# 7_dout.net
KiCad netlist of a schematic drawn in Altium Designer
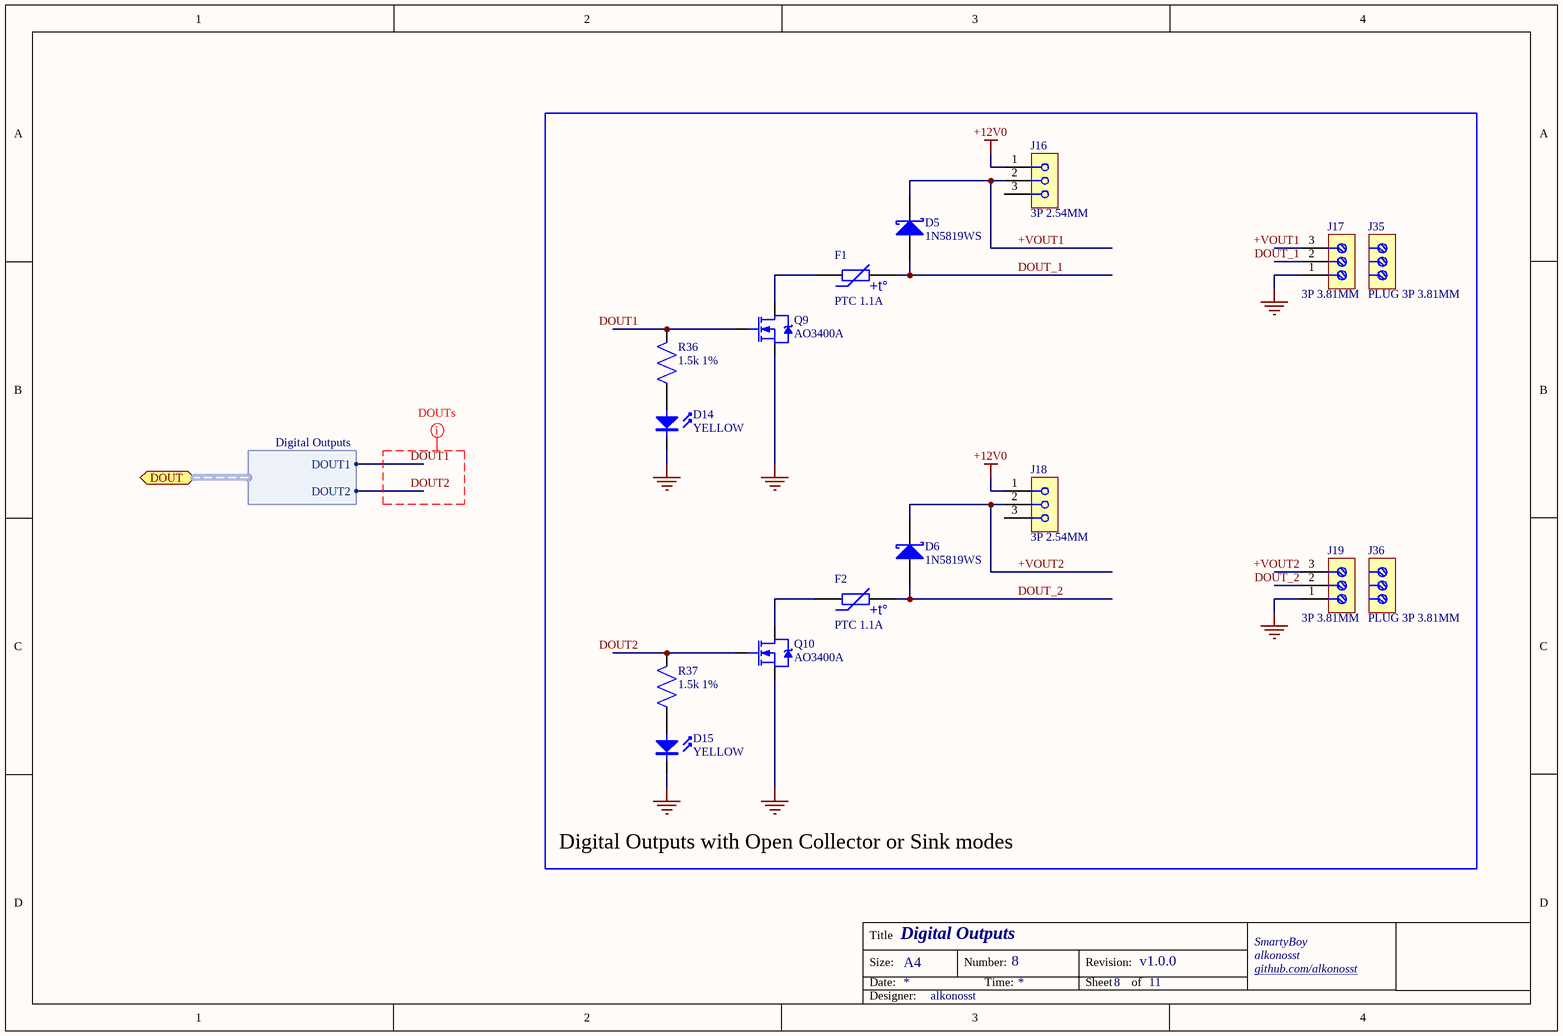
[diagram p0: 7_dout.SchDoc]

(export (version "E")
  (design (tool "Eeschema 10.0.6"))
  (components
    (comp (ref "D5")
      (value "1N5819WS")
      (footprint "SOD-323")
      (description "40V 1A 600mV @ 1A SOD-323 Schottky Barrier Diodes (SBD)")
      (fields (field (name "LCSC PART") "C191023"))
      (libsource (lib "nombre_por_definir") (part "1N5819WS"))
    )
    (comp (ref "D6")
      (value "1N5819WS")
      (footprint "SOD-323")
      (description "40V 1A 600mV @ 1A SOD-323 Schottky Barrier Diodes (SBD)")
      (fields (field (name "LCSC PART") "C191023"))
      (libsource (lib "nombre_por_definir") (part "1N5819WS"))
    )
    (comp (ref "D14")
      (value "YELLOW")
      (footprint "LED0603-YELLOW")
      (description "Yellow 585.5~591.5nm 0603 Light Emitting Diodes (LED)")
      (fields (field (name "LCSC PART") "C72038"))
      (libsource (lib "nombre_por_definir") (part "19-213/Y2C-CQ2R2L/3T(CY)"))
    )
    (comp (ref "D15")
      (value "YELLOW")
      (footprint "LED0603-YELLOW")
      (description "Yellow 585.5~591.5nm 0603 Light Emitting Diodes (LED)")
      (fields (field (name "LCSC PART") "C72038"))
      (libsource (lib "nombre_por_definir") (part "19-213/Y2C-CQ2R2L/3T(CY)"))
    )
    (comp (ref "F1")
      (value "PTC 1.1A")
      (footprint "1812L")
      (description "Polymeric 33V 200mΩ 1.95A 500ms 1812 PTC Resettable Fuses")
      (fields (field (name "LCSC PART") "C142747"))
      (libsource (lib "nombre_por_definir") (part "1812L110/33MR"))
    )
    (comp (ref "F2")
      (value "PTC 1.1A")
      (footprint "1812L")
      (description "Polymeric 33V 200mΩ 1.95A 500ms 1812 PTC Resettable Fuses")
      (fields (field (name "LCSC PART") "C142747"))
      (libsource (lib "nombre_por_definir") (part "1812L110/33MR"))
    )
    (comp (ref "J16")
      (value "3P 2.54MM")
      (footprint "HDR-M-3P-2.54MM")
      (description "3 2.54mm Straight 1 Header，Breakaway Through Hole Pin Header & Female Header")
      (fields (field (name "LCSC PART") "C49257"))
      (libsource (lib "nombre_por_definir") (part "C49257"))
    )
    (comp (ref "J17")
      (value "3P 3.81MM")
      (footprint "TB-3P-3.81MM")
      (description "Terminal Block 3 Positions 3.81MM")
      (libsource (lib "nombre_por_definir") (part "TBLOCK-3P-3.81MM"))
    )
    (comp (ref "J18")
      (value "3P 2.54MM")
      (footprint "HDR-M-3P-2.54MM")
      (description "3 2.54mm Straight 1 Header，Breakaway Through Hole Pin Header & Female Header")
      (fields (field (name "LCSC PART") "C49257"))
      (libsource (lib "nombre_por_definir") (part "C49257"))
    )
    (comp (ref "J19")
      (value "3P 3.81MM")
      (footprint "TB-3P-3.81MM")
      (description "Terminal Block 3 Positions 3.81MM")
      (libsource (lib "nombre_por_definir") (part "TBLOCK-3P-3.81MM"))
    )
    (comp (ref "J35")
      (value "PLUG 3P 3.81MM")
      (footprint "TB-PLUG-3P-3.81MM")
      (description "Terminal block plug 3positions 3.81mm")
      (libsource (lib "nombre_por_definir") (part "PLUG-3P-3.81MM"))
    )
    (comp (ref "J36")
      (value "PLUG 3P 3.81MM")
      (footprint "TB-PLUG-3P-3.81MM")
      (description "Terminal block plug 3positions 3.81mm")
      (libsource (lib "nombre_por_definir") (part "PLUG-3P-3.81MM"))
    )
    (comp (ref "Q9")
      (value "AO3400A")
      (footprint "SOT-23-3")
      (description "1.4W 0.0265Ω 5.7A,10V 30V 5.7A N Channel 1.5V 250uA SOT-23-3L MOSFETs")
      (fields (field (name "LCSC PART") "C20917"))
      (libsource (lib "nombre_por_definir") (part "AO3400A"))
    )
    (comp (ref "Q10")
      (value "AO3400A")
      (footprint "SOT-23-3")
      (description "1.4W 0.0265Ω 5.7A,10V 30V 5.7A N Channel 1.5V 250uA SOT-23-3L MOSFETs")
      (fields (field (name "LCSC PART") "C20917"))
      (libsource (lib "nombre_por_definir") (part "AO3400A"))
    )
    (comp (ref "R36")
      (value "1.5k 1%")
      (footprint "R0603")
      (description "1.5kΩ ±1% ±100ppm/℃ 0.1W 0603 Chip Resistor - Surface Mount")
      (fields (field (name "LCSC PART") "C22843"))
      (libsource (lib "nombre_por_definir") (part "0603WAF1501T5E"))
    )
    (comp (ref "R37")
      (value "1.5k 1%")
      (footprint "R0603")
      (description "1.5kΩ ±1% ±100ppm/℃ 0.1W 0603 Chip Resistor - Surface Mount")
      (fields (field (name "LCSC PART") "C22843"))
      (libsource (lib "nombre_por_definir") (part "0603WAF1501T5E"))
    )
  )
  (nets
    (net (code "3") (name "+12V0") (class "Default")
      (node (ref "J16") (pin "1") (pinfunction "1_1") (pintype "passive"))
      (node (ref "J18") (pin "1") (pinfunction "1_1") (pintype "passive"))
    )
    (net (code "4") (name "/+VOUT1") (class "Default")
      (node (ref "D5") (pin "1") (pinfunction "K_1") (pintype "passive"))
      (node (ref "J16") (pin "2") (pinfunction "2_2") (pintype "passive"))
      (node (ref "J17") (pin "3") (pinfunction "3_3") (pintype "passive"))
    )
    (net (code "5") (name "/+VOUT2") (class "Default")
      (node (ref "D6") (pin "1") (pinfunction "K_1") (pintype "passive"))
      (node (ref "J18") (pin "2") (pinfunction "2_2") (pintype "passive"))
      (node (ref "J19") (pin "3") (pinfunction "3_3") (pintype "passive"))
    )
    (net (code "6") (name "/DOUT1") (class "Default")
      (node (ref "Q9") (pin "1") (pinfunction "G_1") (pintype "passive"))
      (node (ref "R36") (pin "2") (pinfunction "2_2") (pintype "passive"))
    )
    (net (code "7") (name "/DOUT2") (class "Default")
      (node (ref "Q10") (pin "1") (pinfunction "G_1") (pintype "passive"))
      (node (ref "R37") (pin "2") (pinfunction "2_2") (pintype "passive"))
    )
    (net (code "8") (name "/DOUT_1") (class "Default")
      (node (ref "D5") (pin "2") (pinfunction "A_2") (pintype "passive"))
      (node (ref "F1") (pin "2") (pinfunction "2_2") (pintype "passive"))
      (node (ref "J17") (pin "2") (pinfunction "2_2") (pintype "passive"))
    )
    (net (code "9") (name "/DOUT_2") (class "Default")
      (node (ref "D6") (pin "2") (pinfunction "A_2") (pintype "passive"))
      (node (ref "F2") (pin "2") (pinfunction "2_2") (pintype "passive"))
      (node (ref "J19") (pin "2") (pinfunction "2_2") (pintype "passive"))
    )
    (net (code "11") (name "GND") (class "Default")
      (node (ref "D14") (pin "1") (pinfunction "1_1") (pintype "passive"))
      (node (ref "D15") (pin "1") (pinfunction "1_1") (pintype "passive"))
      (node (ref "J17") (pin "1") (pinfunction "1_1") (pintype "passive"))
      (node (ref "J19") (pin "1") (pinfunction "1_1") (pintype "passive"))
      (node (ref "Q10") (pin "2") (pinfunction "S_2") (pintype "passive"))
      (node (ref "Q9") (pin "2") (pinfunction "S_2") (pintype "passive"))
    )
    (net (code "12") (name "Net-(D14-Pad2)") (class "Default")
      (node (ref "D14") (pin "2") (pinfunction "2_2") (pintype "passive"))
      (node (ref "R36") (pin "1") (pinfunction "1_1") (pintype "passive"))
    )
    (net (code "13") (name "Net-(D15-Pad2)") (class "Default")
      (node (ref "D15") (pin "2") (pinfunction "2_2") (pintype "passive"))
      (node (ref "R37") (pin "1") (pinfunction "1_1") (pintype "passive"))
    )
    (net (code "14") (name "Net-(Q9-D)") (class "Default")
      (node (ref "F1") (pin "1") (pinfunction "1_1") (pintype "passive"))
      (node (ref "Q9") (pin "3") (pinfunction "D_3") (pintype "passive"))
    )
    (net (code "15") (name "Net-(Q10-D)") (class "Default")
      (node (ref "F2") (pin "1") (pinfunction "1_1") (pintype "passive"))
      (node (ref "Q10") (pin "3") (pinfunction "D_3") (pintype "passive"))
    )
    (net (code "16") (name "unconnected-(J16-Pad3)") (class "Default")
      (node (ref "J16") (pin "3") (pinfunction "3_3") (pintype "passive"))
    )
    (net (code "17") (name "unconnected-(J18-Pad3)") (class "Default")
      (node (ref "J18") (pin "3") (pinfunction "3_3") (pintype "passive"))
    )
  )
)
